# ASD2002.net
KiCad netlist of a schematic drawn in EAGLE
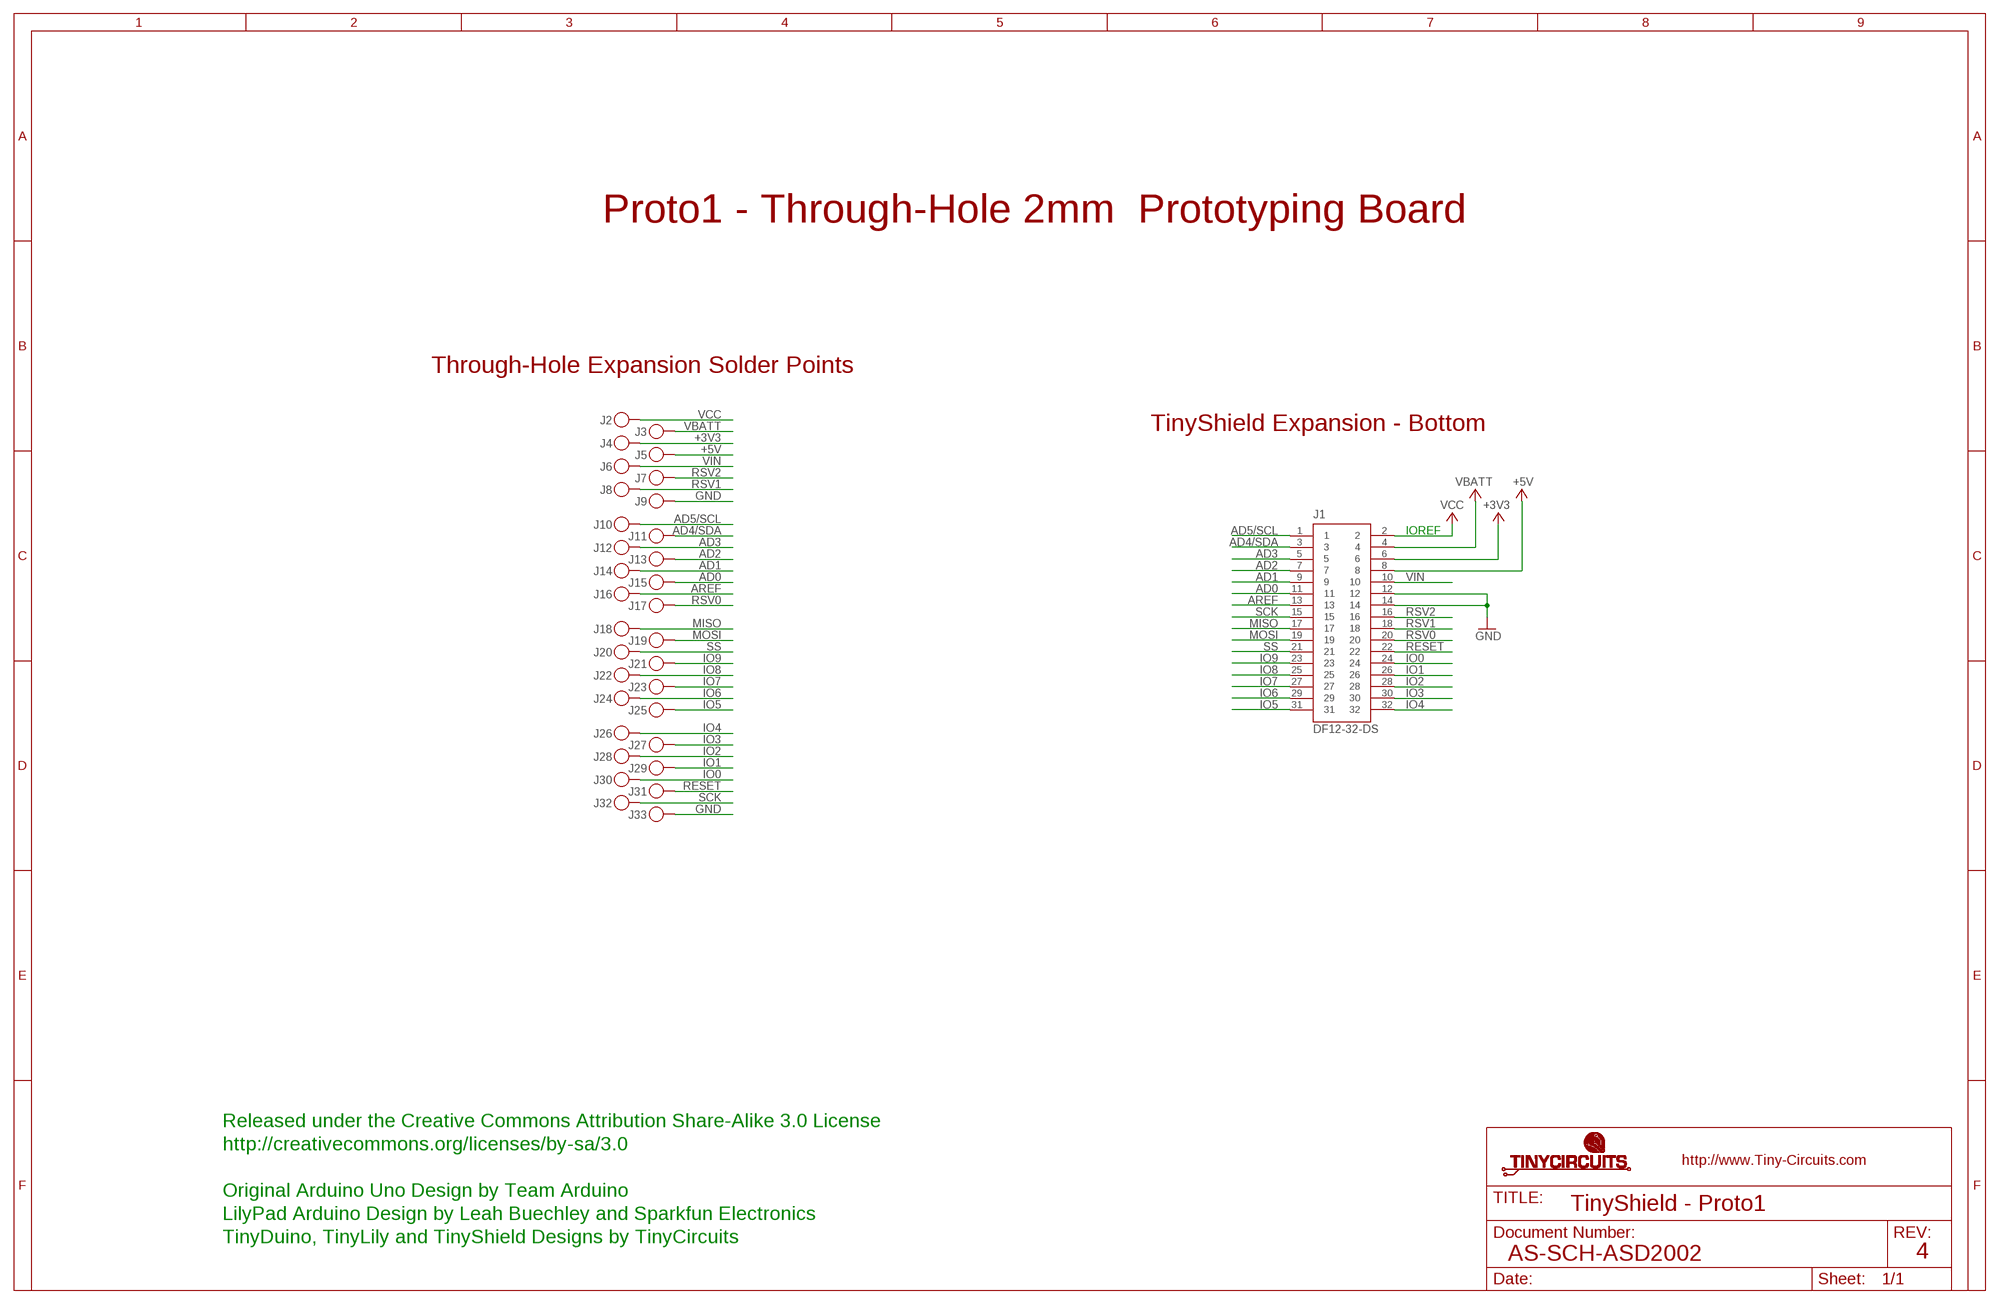
[diagram p0: schematic, sheet 1]

(export (version "E")
  (design (tool "Eeschema 10.0.6"))
  (components
    (comp (ref "J1")
      (value "DF12-32-DS")
      (footprint "eagle-import:DF12-32-DS")
      (fields (field (name "PARTNO") "AS-ITM-00012") (field (name "PARTNO_1") "AS-ITM-00012"))
      (libsource (lib "eagle-import") (part "AS-ITM-00012"))
    )
    (comp (ref "J2")
      (value "PIN_1X.1\"")
      (footprint "eagle-import:1X.1_")
      (fields (field (name "PARTNO") "COPPER"))
      (libsource (lib "eagle-import") (part "PIN_1X.1{dblquote}"))
    )
    (comp (ref "J3")
      (value "PIN_1X.1\"")
      (footprint "eagle-import:1X.1_")
      (fields (field (name "PARTNO") "COPPER"))
      (libsource (lib "eagle-import") (part "PIN_1X.1{dblquote}"))
    )
    (comp (ref "J4")
      (value "PIN_1X.1\"")
      (footprint "eagle-import:1X.1_")
      (fields (field (name "PARTNO") "COPPER"))
      (libsource (lib "eagle-import") (part "PIN_1X.1{dblquote}"))
    )
    (comp (ref "J5")
      (value "PIN_1X.1\"")
      (footprint "eagle-import:1X.1_")
      (fields (field (name "PARTNO") "COPPER"))
      (libsource (lib "eagle-import") (part "PIN_1X.1{dblquote}"))
    )
    (comp (ref "J6")
      (value "PIN_1X.1\"")
      (footprint "eagle-import:1X.1_")
      (fields (field (name "PARTNO") "COPPER"))
      (libsource (lib "eagle-import") (part "PIN_1X.1{dblquote}"))
    )
    (comp (ref "J7")
      (value "PIN_1X.1\"")
      (footprint "eagle-import:1X.1_")
      (fields (field (name "PARTNO") "COPPER"))
      (libsource (lib "eagle-import") (part "PIN_1X.1{dblquote}"))
    )
    (comp (ref "J8")
      (value "PIN_1X.1\"")
      (footprint "eagle-import:1X.1_")
      (fields (field (name "PARTNO") "COPPER"))
      (libsource (lib "eagle-import") (part "PIN_1X.1{dblquote}"))
    )
    (comp (ref "J9")
      (value "PIN_1X.1\"")
      (footprint "eagle-import:1X.1_")
      (fields (field (name "PARTNO") "COPPER"))
      (libsource (lib "eagle-import") (part "PIN_1X.1{dblquote}"))
    )
    (comp (ref "J10")
      (value "PIN_1X.1\"")
      (footprint "eagle-import:1X.1_")
      (fields (field (name "PARTNO") "COPPER"))
      (libsource (lib "eagle-import") (part "PIN_1X.1{dblquote}"))
    )
    (comp (ref "J11")
      (value "PIN_1X.1\"")
      (footprint "eagle-import:1X.1_")
      (fields (field (name "PARTNO") "COPPER"))
      (libsource (lib "eagle-import") (part "PIN_1X.1{dblquote}"))
    )
    (comp (ref "J12")
      (value "PIN_1X.1\"")
      (footprint "eagle-import:1X.1_")
      (fields (field (name "PARTNO") "COPPER"))
      (libsource (lib "eagle-import") (part "PIN_1X.1{dblquote}"))
    )
    (comp (ref "J13")
      (value "PIN_1X.1\"")
      (footprint "eagle-import:1X.1_")
      (fields (field (name "PARTNO") "COPPER"))
      (libsource (lib "eagle-import") (part "PIN_1X.1{dblquote}"))
    )
    (comp (ref "J14")
      (value "PIN_1X.1\"")
      (footprint "eagle-import:1X.1_")
      (fields (field (name "PARTNO") "COPPER"))
      (libsource (lib "eagle-import") (part "PIN_1X.1{dblquote}"))
    )
    (comp (ref "J15")
      (value "PIN_1X.1\"")
      (footprint "eagle-import:1X.1_")
      (fields (field (name "PARTNO") "COPPER"))
      (libsource (lib "eagle-import") (part "PIN_1X.1{dblquote}"))
    )
    (comp (ref "J16")
      (value "PIN_1X.1\"")
      (footprint "eagle-import:1X.1_")
      (fields (field (name "PARTNO") "COPPER"))
      (libsource (lib "eagle-import") (part "PIN_1X.1{dblquote}"))
    )
    (comp (ref "J17")
      (value "PIN_1X.1\"")
      (footprint "eagle-import:1X.1_")
      (fields (field (name "PARTNO") "COPPER"))
      (libsource (lib "eagle-import") (part "PIN_1X.1{dblquote}"))
    )
    (comp (ref "J18")
      (value "PIN_1X.1\"")
      (footprint "eagle-import:1X.1_")
      (fields (field (name "PARTNO") "COPPER"))
      (libsource (lib "eagle-import") (part "PIN_1X.1{dblquote}"))
    )
    (comp (ref "J19")
      (value "PIN_1X.1\"")
      (footprint "eagle-import:1X.1_")
      (fields (field (name "PARTNO") "COPPER"))
      (libsource (lib "eagle-import") (part "PIN_1X.1{dblquote}"))
    )
    (comp (ref "J20")
      (value "PIN_1X.1\"")
      (footprint "eagle-import:1X.1_")
      (fields (field (name "PARTNO") "COPPER"))
      (libsource (lib "eagle-import") (part "PIN_1X.1{dblquote}"))
    )
    (comp (ref "J21")
      (value "PIN_1X.1\"")
      (footprint "eagle-import:1X.1_")
      (fields (field (name "PARTNO") "COPPER"))
      (libsource (lib "eagle-import") (part "PIN_1X.1{dblquote}"))
    )
    (comp (ref "J22")
      (value "PIN_1X.1\"")
      (footprint "eagle-import:1X.1_")
      (fields (field (name "PARTNO") "COPPER"))
      (libsource (lib "eagle-import") (part "PIN_1X.1{dblquote}"))
    )
    (comp (ref "J23")
      (value "PIN_1X.1\"")
      (footprint "eagle-import:1X.1_")
      (fields (field (name "PARTNO") "COPPER"))
      (libsource (lib "eagle-import") (part "PIN_1X.1{dblquote}"))
    )
    (comp (ref "J24")
      (value "PIN_1X.1\"")
      (footprint "eagle-import:1X.1_")
      (fields (field (name "PARTNO") "COPPER"))
      (libsource (lib "eagle-import") (part "PIN_1X.1{dblquote}"))
    )
    (comp (ref "J25")
      (value "PIN_1X.1\"")
      (footprint "eagle-import:1X.1_")
      (fields (field (name "PARTNO") "COPPER"))
      (libsource (lib "eagle-import") (part "PIN_1X.1{dblquote}"))
    )
    (comp (ref "J26")
      (value "PIN_1X.1\"")
      (footprint "eagle-import:1X.1_")
      (fields (field (name "PARTNO") "COPPER"))
      (libsource (lib "eagle-import") (part "PIN_1X.1{dblquote}"))
    )
    (comp (ref "J27")
      (value "PIN_1X.1\"")
      (footprint "eagle-import:1X.1_")
      (fields (field (name "PARTNO") "COPPER"))
      (libsource (lib "eagle-import") (part "PIN_1X.1{dblquote}"))
    )
    (comp (ref "J28")
      (value "PIN_1X.1\"")
      (footprint "eagle-import:1X.1_")
      (fields (field (name "PARTNO") "COPPER"))
      (libsource (lib "eagle-import") (part "PIN_1X.1{dblquote}"))
    )
    (comp (ref "J29")
      (value "PIN_1X.1\"")
      (footprint "eagle-import:1X.1_")
      (fields (field (name "PARTNO") "COPPER"))
      (libsource (lib "eagle-import") (part "PIN_1X.1{dblquote}"))
    )
    (comp (ref "J30")
      (value "PIN_1X.1\"")
      (footprint "eagle-import:1X.1_")
      (fields (field (name "PARTNO") "COPPER"))
      (libsource (lib "eagle-import") (part "PIN_1X.1{dblquote}"))
    )
    (comp (ref "J31")
      (value "PIN_1X.1\"")
      (footprint "eagle-import:1X.1_")
      (fields (field (name "PARTNO") "COPPER"))
      (libsource (lib "eagle-import") (part "PIN_1X.1{dblquote}"))
    )
    (comp (ref "J32")
      (value "PIN_1X.1\"")
      (footprint "eagle-import:1X.1_")
      (fields (field (name "PARTNO") "COPPER"))
      (libsource (lib "eagle-import") (part "PIN_1X.1{dblquote}"))
    )
    (comp (ref "J33")
      (value "PIN_1X.1\"")
      (footprint "eagle-import:1X.1_")
      (fields (field (name "PARTNO") "COPPER"))
      (libsource (lib "eagle-import") (part "PIN_1X.1{dblquote}"))
    )
  )
  (nets
    (net (code "1") (name "+3V3") (class "Default")
      (node (ref "J1") (pin "6") (pinfunction "6_6") (pintype "bidirectional"))
      (node (ref "J4") (pin "1") (pinfunction "1_1") (pintype "bidirectional"))
    )
    (net (code "2") (name "+5V") (class "Default")
      (node (ref "J1") (pin "8") (pinfunction "8_8") (pintype "bidirectional"))
      (node (ref "J5") (pin "1") (pinfunction "1_1") (pintype "bidirectional"))
    )
    (net (code "3") (name "/AD0") (class "Default")
      (node (ref "J1") (pin "11") (pinfunction "11_11") (pintype "bidirectional"))
      (node (ref "J15") (pin "1") (pinfunction "1_1") (pintype "bidirectional"))
    )
    (net (code "4") (name "/AD1") (class "Default")
      (node (ref "J1") (pin "9") (pinfunction "9_9") (pintype "bidirectional"))
      (node (ref "J14") (pin "1") (pinfunction "1_1") (pintype "bidirectional"))
    )
    (net (code "5") (name "/AD2") (class "Default")
      (node (ref "J1") (pin "7") (pinfunction "7_7") (pintype "bidirectional"))
      (node (ref "J13") (pin "1") (pinfunction "1_1") (pintype "bidirectional"))
    )
    (net (code "6") (name "/AD3") (class "Default")
      (node (ref "J1") (pin "5") (pinfunction "5_5") (pintype "bidirectional"))
      (node (ref "J12") (pin "1") (pinfunction "1_1") (pintype "bidirectional"))
    )
    (net (code "7") (name "/AD4{slash}SDA") (class "Default")
      (node (ref "J1") (pin "3") (pinfunction "3_3") (pintype "bidirectional"))
      (node (ref "J11") (pin "1") (pinfunction "1_1") (pintype "bidirectional"))
    )
    (net (code "8") (name "/AD5{slash}SCL") (class "Default")
      (node (ref "J1") (pin "1") (pinfunction "1_1") (pintype "bidirectional"))
      (node (ref "J10") (pin "1") (pinfunction "1_1") (pintype "bidirectional"))
    )
    (net (code "9") (name "/AREF") (class "Default")
      (node (ref "J1") (pin "13") (pinfunction "13_13") (pintype "bidirectional"))
      (node (ref "J16") (pin "1") (pinfunction "1_1") (pintype "bidirectional"))
    )
    (net (code "10") (name "/IO0") (class "Default")
      (node (ref "J1") (pin "24") (pinfunction "24_24") (pintype "bidirectional"))
      (node (ref "J30") (pin "1") (pinfunction "1_1") (pintype "bidirectional"))
    )
    (net (code "11") (name "/IO1") (class "Default")
      (node (ref "J1") (pin "26") (pinfunction "26_26") (pintype "bidirectional"))
      (node (ref "J29") (pin "1") (pinfunction "1_1") (pintype "bidirectional"))
    )
    (net (code "12") (name "/IO2") (class "Default")
      (node (ref "J1") (pin "28") (pinfunction "28_28") (pintype "bidirectional"))
      (node (ref "J28") (pin "1") (pinfunction "1_1") (pintype "bidirectional"))
    )
    (net (code "13") (name "/IO3") (class "Default")
      (node (ref "J1") (pin "30") (pinfunction "30_30") (pintype "bidirectional"))
      (node (ref "J27") (pin "1") (pinfunction "1_1") (pintype "bidirectional"))
    )
    (net (code "14") (name "/IO4") (class "Default")
      (node (ref "J1") (pin "32") (pinfunction "32_32") (pintype "bidirectional"))
      (node (ref "J26") (pin "1") (pinfunction "1_1") (pintype "bidirectional"))
    )
    (net (code "15") (name "/IO5") (class "Default")
      (node (ref "J1") (pin "31") (pinfunction "31_31") (pintype "bidirectional"))
      (node (ref "J25") (pin "1") (pinfunction "1_1") (pintype "bidirectional"))
    )
    (net (code "16") (name "/IO6") (class "Default")
      (node (ref "J1") (pin "29") (pinfunction "29_29") (pintype "bidirectional"))
      (node (ref "J24") (pin "1") (pinfunction "1_1") (pintype "bidirectional"))
    )
    (net (code "17") (name "/IO7") (class "Default")
      (node (ref "J1") (pin "27") (pinfunction "27_27") (pintype "bidirectional"))
      (node (ref "J23") (pin "1") (pinfunction "1_1") (pintype "bidirectional"))
    )
    (net (code "18") (name "/IO8") (class "Default")
      (node (ref "J1") (pin "25") (pinfunction "25_25") (pintype "bidirectional"))
      (node (ref "J22") (pin "1") (pinfunction "1_1") (pintype "bidirectional"))
    )
    (net (code "19") (name "/IO9") (class "Default")
      (node (ref "J1") (pin "23") (pinfunction "23_23") (pintype "bidirectional"))
      (node (ref "J21") (pin "1") (pinfunction "1_1") (pintype "bidirectional"))
    )
    (net (code "20") (name "/MISO") (class "Default")
      (node (ref "J1") (pin "17") (pinfunction "17_17") (pintype "bidirectional"))
      (node (ref "J18") (pin "1") (pinfunction "1_1") (pintype "bidirectional"))
    )
    (net (code "21") (name "/MOSI") (class "Default")
      (node (ref "J1") (pin "19") (pinfunction "19_19") (pintype "bidirectional"))
      (node (ref "J19") (pin "1") (pinfunction "1_1") (pintype "bidirectional"))
    )
    (net (code "22") (name "/RESET") (class "Default")
      (node (ref "J1") (pin "22") (pinfunction "22_22") (pintype "bidirectional"))
      (node (ref "J31") (pin "1") (pinfunction "1_1") (pintype "bidirectional"))
    )
    (net (code "23") (name "/RSV0") (class "Default")
      (node (ref "J1") (pin "20") (pinfunction "20_20") (pintype "bidirectional"))
      (node (ref "J17") (pin "1") (pinfunction "1_1") (pintype "bidirectional"))
    )
    (net (code "24") (name "/RSV1") (class "Default")
      (node (ref "J1") (pin "18") (pinfunction "18_18") (pintype "bidirectional"))
      (node (ref "J8") (pin "1") (pinfunction "1_1") (pintype "bidirectional"))
    )
    (net (code "25") (name "/RSV2") (class "Default")
      (node (ref "J1") (pin "16") (pinfunction "16_16") (pintype "bidirectional"))
      (node (ref "J7") (pin "1") (pinfunction "1_1") (pintype "bidirectional"))
    )
    (net (code "26") (name "/SCK") (class "Default")
      (node (ref "J1") (pin "15") (pinfunction "15_15") (pintype "bidirectional"))
      (node (ref "J32") (pin "1") (pinfunction "1_1") (pintype "bidirectional"))
    )
    (net (code "27") (name "/SS") (class "Default")
      (node (ref "J1") (pin "21") (pinfunction "21_21") (pintype "bidirectional"))
      (node (ref "J20") (pin "1") (pinfunction "1_1") (pintype "bidirectional"))
    )
    (net (code "28") (name "/VIN") (class "Default")
      (node (ref "J1") (pin "10") (pinfunction "10_10") (pintype "bidirectional"))
      (node (ref "J6") (pin "1") (pinfunction "1_1") (pintype "bidirectional"))
    )
    (net (code "29") (name "GND") (class "Default")
      (node (ref "J1") (pin "12") (pinfunction "12_12") (pintype "bidirectional"))
      (node (ref "J1") (pin "14") (pinfunction "14_14") (pintype "bidirectional"))
      (node (ref "J33") (pin "1") (pinfunction "1_1") (pintype "bidirectional"))
      (node (ref "J9") (pin "1") (pinfunction "1_1") (pintype "bidirectional"))
    )
    (net (code "30") (name "VBATT") (class "Default")
      (node (ref "J1") (pin "4") (pinfunction "4_4") (pintype "bidirectional"))
      (node (ref "J3") (pin "1") (pinfunction "1_1") (pintype "bidirectional"))
    )
    (net (code "31") (name "VCC") (class "Default")
      (node (ref "J1") (pin "2") (pinfunction "2_2") (pintype "bidirectional"))
      (node (ref "J2") (pin "1") (pinfunction "1_1") (pintype "bidirectional"))
    )
  )
)
